# Mega_Shield_enjaksa.net
KiCad netlist of a schematic drawn in EAGLE
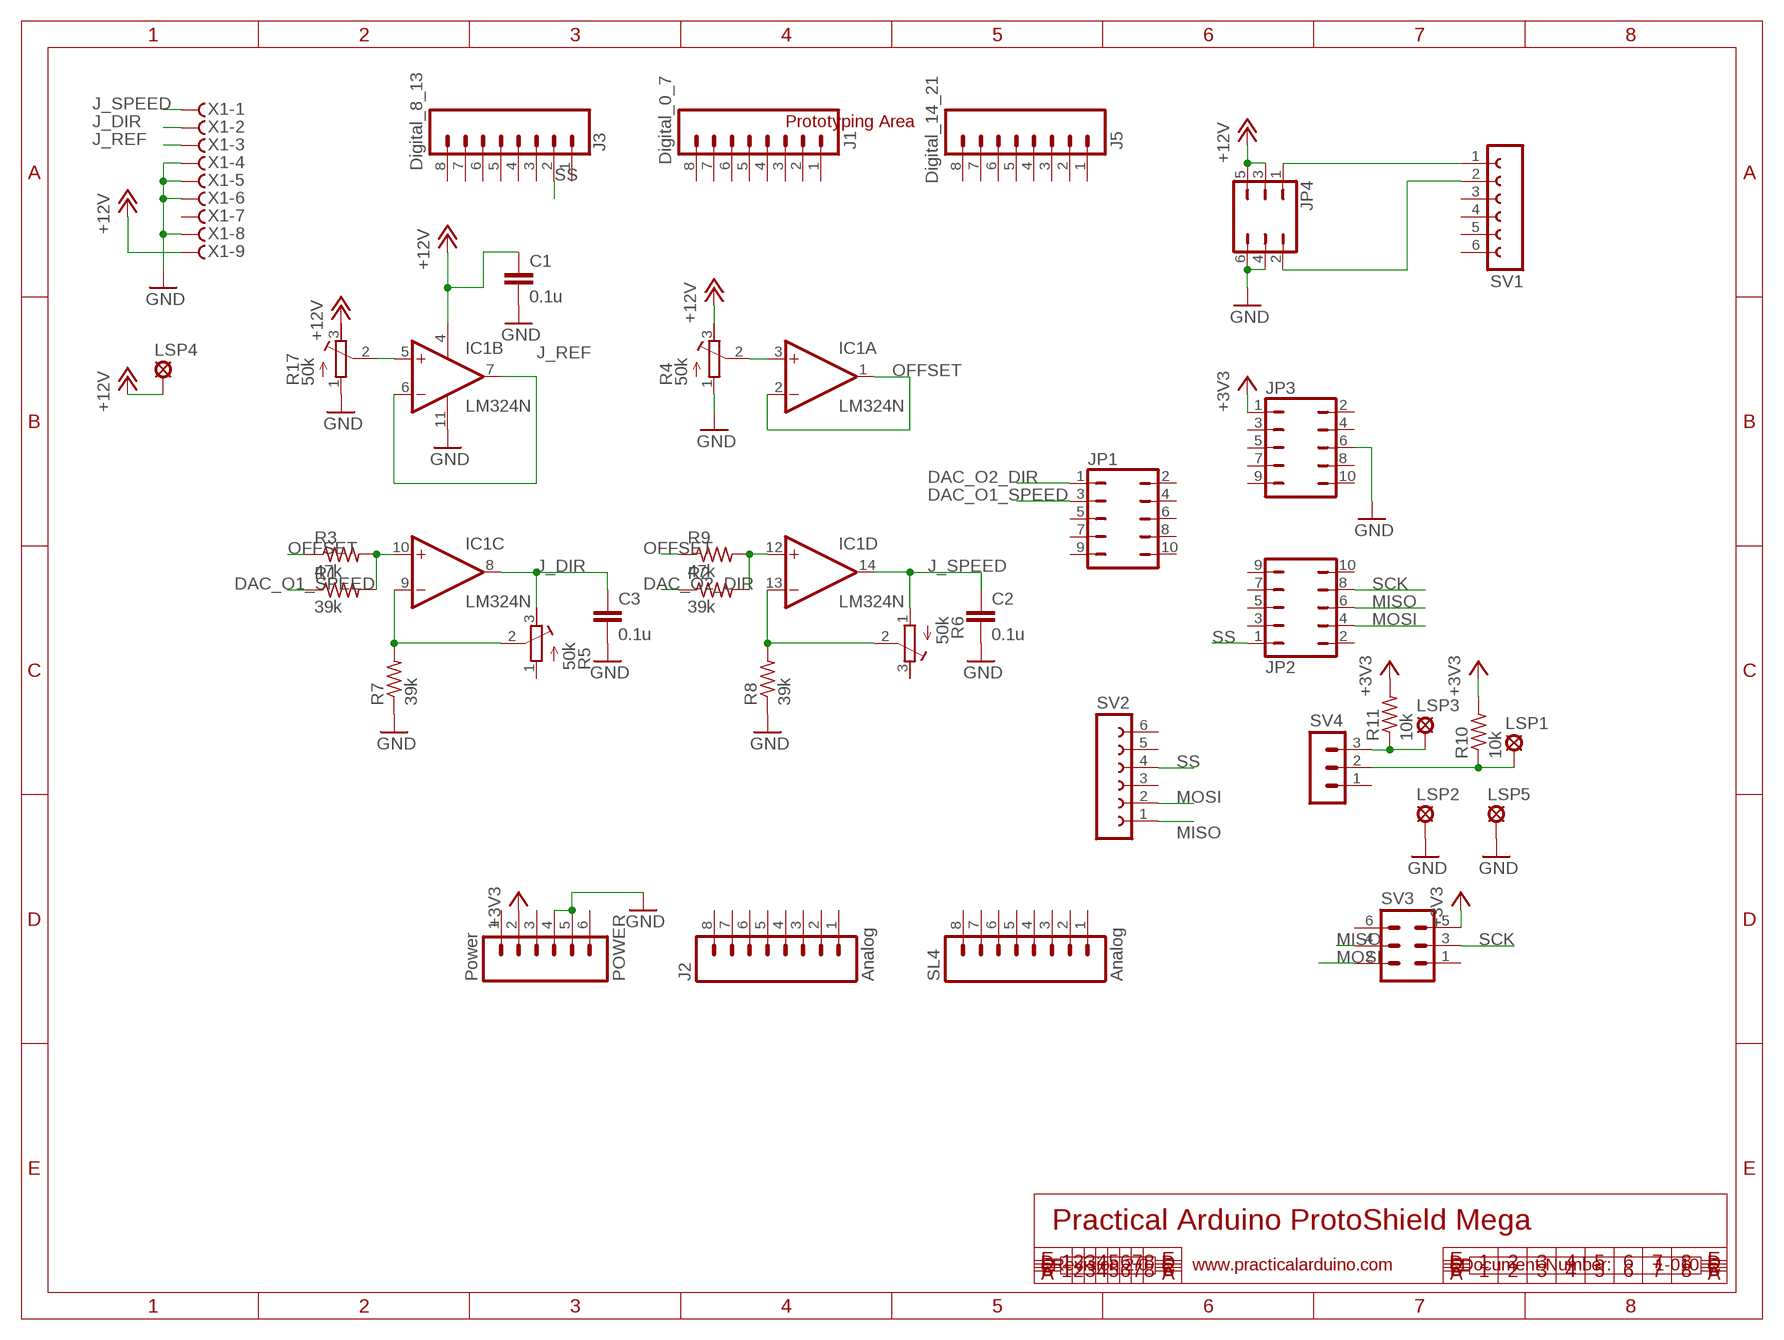
[diagram p0: schematic, sheet 1]

(export (version "E")
  (design (tool "Eeschema 10.0.6"))
  (components
    (comp (ref "C1")
      (value "0.1u")
      (footprint "eagle-import:C025-024X044")
      (libsource (lib "eagle-import") (part "C-EU025-024X044"))
    )
    (comp (ref "C2")
      (value "0.1u")
      (footprint "eagle-import:C050-025X075")
      (libsource (lib "eagle-import") (part "C-EU050-025X075"))
    )
    (comp (ref "C3")
      (value "0.1u")
      (footprint "eagle-import:C025-024X044")
      (libsource (lib "eagle-import") (part "C-EU025-024X044"))
    )
    (comp (ref "IC1")
      (value "LM324N")
      (footprint "eagle-import:DIL14")
      (libsource (lib "eagle-import") (part "LM324N"))
    )
    (comp (ref "J1")
      (value "Digital_0_7")
      (footprint "eagle-import:1X08")
      (libsource (lib "eagle-import") (part "M08"))
    )
    (comp (ref "J2")
      (value "Analog")
      (footprint "eagle-import:1X08")
      (libsource (lib "eagle-import") (part "M08"))
    )
    (comp (ref "J3")
      (value "Digital_8_13")
      (footprint "eagle-import:1X08")
      (libsource (lib "eagle-import") (part "M08"))
    )
    (comp (ref "J5")
      (value "Digital_14_21")
      (footprint "eagle-import:1X08")
      (libsource (lib "eagle-import") (part "M08"))
    )
    (comp (ref "JP1")
      (value "JP5Q")
      (footprint "eagle-import:JP5Q")
      (libsource (lib "eagle-import") (part "JP5Q"))
    )
    (comp (ref "JP2")
      (value "JP5Q")
      (footprint "eagle-import:JP5Q")
      (libsource (lib "eagle-import") (part "JP5Q"))
    )
    (comp (ref "JP3")
      (value "JP5Q")
      (footprint "eagle-import:JP5Q")
      (libsource (lib "eagle-import") (part "JP5Q"))
    )
    (comp (ref "JP4")
      (value "JP3Q")
      (footprint "eagle-import:JP3Q")
      (libsource (lib "eagle-import") (part "JP3Q"))
    )
    (comp (ref "LSP1")
      (value "SE13")
      (footprint "eagle-import:SE13")
      (libsource (lib "eagle-import") (part "SE13"))
    )
    (comp (ref "LSP2")
      (value "SE13")
      (footprint "eagle-import:SE13")
      (libsource (lib "eagle-import") (part "SE13"))
    )
    (comp (ref "LSP3")
      (value "SE13")
      (footprint "eagle-import:SE13")
      (libsource (lib "eagle-import") (part "SE13"))
    )
    (comp (ref "LSP4")
      (value "SE13")
      (footprint "eagle-import:SE13")
      (libsource (lib "eagle-import") (part "SE13"))
    )
    (comp (ref "LSP5")
      (value "SE13")
      (footprint "eagle-import:SE13")
      (libsource (lib "eagle-import") (part "SE13"))
    )
    (comp (ref "POWER")
      (value "Power")
      (footprint "eagle-import:1X06")
      (libsource (lib "eagle-import") (part "M06SIP"))
    )
    (comp (ref "R1")
      (value "39k")
      (footprint "eagle-import:0204_7")
      (libsource (lib "eagle-import") (part "R-US_0204/7"))
    )
    (comp (ref "R2")
      (value "39k")
      (footprint "eagle-import:0204_7")
      (libsource (lib "eagle-import") (part "R-US_0204/7"))
    )
    (comp (ref "R3")
      (value "47k")
      (footprint "eagle-import:0204_7")
      (libsource (lib "eagle-import") (part "R-US_0204/7"))
    )
    (comp (ref "R4")
      (value "50k")
      (footprint "eagle-import:RTRIM64W")
      (libsource (lib "eagle-import") (part "R-TRIMM64W"))
    )
    (comp (ref "R5")
      (value "50k")
      (footprint "eagle-import:RTRIM64W")
      (libsource (lib "eagle-import") (part "R-TRIMM64W"))
    )
    (comp (ref "R6")
      (value "50k")
      (footprint "eagle-import:RTRIM64W")
      (libsource (lib "eagle-import") (part "R-TRIMM64W"))
    )
    (comp (ref "R7")
      (value "39k")
      (footprint "eagle-import:0204_7")
      (libsource (lib "eagle-import") (part "R-US_0204/7"))
    )
    (comp (ref "R8")
      (value "39k")
      (footprint "eagle-import:0204V")
      (libsource (lib "eagle-import") (part "R-US_0204/2V"))
    )
    (comp (ref "R9")
      (value "47k")
      (footprint "eagle-import:0204_7")
      (libsource (lib "eagle-import") (part "R-US_0204/7"))
    )
    (comp (ref "R10")
      (value "10k")
      (footprint "eagle-import:0204V")
      (libsource (lib "eagle-import") (part "R-US_0204/2V"))
    )
    (comp (ref "R11")
      (value "10k")
      (footprint "eagle-import:0204V")
      (libsource (lib "eagle-import") (part "R-US_0204/2V"))
    )
    (comp (ref "R17")
      (value "50k")
      (footprint "eagle-import:RTRIM64W")
      (libsource (lib "eagle-import") (part "R-TRIMM64W"))
    )
    (comp (ref "SL4")
      (value "Analog")
      (footprint "eagle-import:1X08")
      (libsource (lib "eagle-import") (part "M08"))
    )
    (comp (ref "SV1")
      (value "FE06-1")
      (footprint "eagle-import:FE06")
      (libsource (lib "eagle-import") (part "FE06-1"))
    )
    (comp (ref "SV2")
      (value "FE06-1")
      (footprint "eagle-import:FE06")
      (libsource (lib "eagle-import") (part "FE06-1"))
    )
    (comp (ref "SV3")
      (value "MA03-2")
      (footprint "eagle-import:MA03-2")
      (libsource (lib "eagle-import") (part "MA03-2"))
    )
    (comp (ref "SV4")
      (value "MA03-1")
      (footprint "eagle-import:MA03-1")
      (libsource (lib "eagle-import") (part "MA03-1"))
    )
    (comp (ref "X1")
      (value "F09HS")
      (footprint "eagle-import:F09H")
      (libsource (lib "eagle-import") (part "F09?SH"))
    )
  )
  (nets
    (net (code "1") (name "+3V3") (class "Default")
      (node (ref "JP3") (pin "1") (pinfunction "1_1") (pintype "passive"))
      (node (ref "POWER") (pin "2") (pinfunction "2_2") (pintype "passive"))
      (node (ref "R10") (pin "2") (pinfunction "2_2") (pintype "passive"))
      (node (ref "R11") (pin "2") (pinfunction "2_2") (pintype "passive"))
      (node (ref "SV3") (pin "5") (pinfunction "5_5") (pintype "passive"))
    )
    (net (code "2") (name "+12V") (class "Default")
      (node (ref "C1") (pin "1") (pinfunction "1_1") (pintype "passive"))
      (node (ref "IC1") (pin "4") (pinfunction "V+_4") (pintype "power_in"))
      (node (ref "JP4") (pin "3") (pinfunction "3_3") (pintype "passive"))
      (node (ref "JP4") (pin "5") (pinfunction "5_5") (pintype "passive"))
      (node (ref "LSP4") (pin "MP") (pinfunction "MP_MP") (pintype "passive"))
      (node (ref "R17") (pin "3") (pinfunction "E_3") (pintype "passive"))
      (node (ref "R4") (pin "3") (pinfunction "E_3") (pintype "passive"))
      (node (ref "X1") (pin "9") (pinfunction "F_9") (pintype "passive"))
    )
    (net (code "3") (name "/DAC_O1_SPEED") (class "Default")
      (node (ref "JP1") (pin "3") (pinfunction "3_3") (pintype "passive"))
      (node (ref "R1") (pin "1") (pinfunction "1_1") (pintype "passive"))
    )
    (net (code "4") (name "/DAC_O2_DIR") (class "Default")
      (node (ref "JP1") (pin "1") (pinfunction "1_1") (pintype "passive"))
      (node (ref "R2") (pin "1") (pinfunction "1_1") (pintype "passive"))
    )
    (net (code "5") (name "/J_DIR") (class "Default")
      (node (ref "C3") (pin "1") (pinfunction "1_1") (pintype "passive"))
      (node (ref "IC1") (pin "8") (pinfunction "OUT_8") (pintype "output"))
      (node (ref "R5") (pin "3") (pinfunction "E_3") (pintype "passive"))
      (node (ref "X1") (pin "2") (pinfunction "F_2") (pintype "passive"))
    )
    (net (code "6") (name "/J_REF") (class "Default")
      (node (ref "IC1") (pin "6") (pinfunction "-IN_6") (pintype "input"))
      (node (ref "IC1") (pin "7") (pinfunction "OUT_7") (pintype "output"))
      (node (ref "X1") (pin "3") (pinfunction "F_3") (pintype "passive"))
    )
    (net (code "7") (name "/J_SPEED") (class "Default")
      (node (ref "C2") (pin "1") (pinfunction "1_1") (pintype "passive"))
      (node (ref "IC1") (pin "14") (pinfunction "OUT_14") (pintype "output"))
      (node (ref "R6") (pin "1") (pinfunction "A_1") (pintype "passive"))
      (node (ref "X1") (pin "1") (pinfunction "F_1") (pintype "passive"))
    )
    (net (code "8") (name "/MISO") (class "Default")
      (node (ref "JP2") (pin "6") (pinfunction "6_6") (pintype "passive"))
      (node (ref "SV2") (pin "1") (pinfunction "1_1") (pintype "passive"))
      (node (ref "SV3") (pin "4") (pinfunction "4_4") (pintype "passive"))
    )
    (net (code "9") (name "/MOSI") (class "Default")
      (node (ref "JP2") (pin "4") (pinfunction "4_4") (pintype "passive"))
      (node (ref "SV2") (pin "2") (pinfunction "2_2") (pintype "passive"))
      (node (ref "SV3") (pin "2") (pinfunction "2_2") (pintype "passive"))
    )
    (net (code "10") (name "/OFFSET") (class "Default")
      (node (ref "IC1") (pin "1") (pinfunction "OUT_1") (pintype "output"))
      (node (ref "IC1") (pin "2") (pinfunction "-IN_2") (pintype "input"))
      (node (ref "R3") (pin "1") (pinfunction "1_1") (pintype "passive"))
      (node (ref "R9") (pin "1") (pinfunction "1_1") (pintype "passive"))
    )
    (net (code "11") (name "/SCK") (class "Default")
      (node (ref "JP2") (pin "8") (pinfunction "8_8") (pintype "passive"))
      (node (ref "SV3") (pin "3") (pinfunction "3_3") (pintype "passive"))
    )
    (net (code "12") (name "/SS") (class "Default")
      (node (ref "J3") (pin "2") (pinfunction "2_2") (pintype "passive"))
      (node (ref "JP2") (pin "1") (pinfunction "1_1") (pintype "passive"))
      (node (ref "SV2") (pin "4") (pinfunction "4_4") (pintype "passive"))
    )
    (net (code "13") (name "GND") (class "Default")
      (node (ref "C1") (pin "2") (pinfunction "2_2") (pintype "passive"))
      (node (ref "C2") (pin "2") (pinfunction "2_2") (pintype "passive"))
      (node (ref "C3") (pin "2") (pinfunction "2_2") (pintype "passive"))
      (node (ref "IC1") (pin "11") (pinfunction "V-_11") (pintype "power_in"))
      (node (ref "JP3") (pin "6") (pinfunction "6_6") (pintype "passive"))
      (node (ref "JP4") (pin "4") (pinfunction "4_4") (pintype "passive"))
      (node (ref "JP4") (pin "6") (pinfunction "6_6") (pintype "passive"))
      (node (ref "LSP2") (pin "MP") (pinfunction "MP_MP") (pintype "passive"))
      (node (ref "LSP5") (pin "MP") (pinfunction "MP_MP") (pintype "passive"))
      (node (ref "POWER") (pin "4") (pinfunction "4_4") (pintype "passive"))
      (node (ref "POWER") (pin "5") (pinfunction "5_5") (pintype "passive"))
      (node (ref "R17") (pin "1") (pinfunction "A_1") (pintype "passive"))
      (node (ref "R4") (pin "1") (pinfunction "A_1") (pintype "passive"))
      (node (ref "R7") (pin "1") (pinfunction "1_1") (pintype "passive"))
      (node (ref "R8") (pin "1") (pinfunction "1_1") (pintype "passive"))
      (node (ref "X1") (pin "4") (pinfunction "F_4") (pintype "passive"))
      (node (ref "X1") (pin "5") (pinfunction "F_5") (pintype "passive"))
      (node (ref "X1") (pin "6") (pinfunction "F_6") (pintype "passive"))
      (node (ref "X1") (pin "8") (pinfunction "F_8") (pintype "passive"))
    )
    (net (code "14") (name "Net-(IC1A-+IN)") (class "Default")
      (node (ref "IC1") (pin "3") (pinfunction "+IN_3") (pintype "input"))
      (node (ref "R4") (pin "2") (pinfunction "S_2") (pintype "passive"))
    )
    (net (code "15") (name "Net-(IC1B-+IN)") (class "Default")
      (node (ref "IC1") (pin "5") (pinfunction "+IN_5") (pintype "input"))
      (node (ref "R17") (pin "2") (pinfunction "S_2") (pintype "passive"))
    )
    (net (code "16") (name "Net-(IC1C-+IN)") (class "Default")
      (node (ref "IC1") (pin "10") (pinfunction "+IN_10") (pintype "input"))
      (node (ref "R1") (pin "2") (pinfunction "2_2") (pintype "passive"))
      (node (ref "R3") (pin "2") (pinfunction "2_2") (pintype "passive"))
    )
    (net (code "17") (name "Net-(IC1C--IN)") (class "Default")
      (node (ref "IC1") (pin "9") (pinfunction "-IN_9") (pintype "input"))
      (node (ref "R5") (pin "2") (pinfunction "S_2") (pintype "passive"))
      (node (ref "R7") (pin "2") (pinfunction "2_2") (pintype "passive"))
    )
    (net (code "18") (name "Net-(IC1D-+IN)") (class "Default")
      (node (ref "IC1") (pin "12") (pinfunction "+IN_12") (pintype "input"))
      (node (ref "R2") (pin "2") (pinfunction "2_2") (pintype "passive"))
      (node (ref "R9") (pin "2") (pinfunction "2_2") (pintype "passive"))
    )
    (net (code "19") (name "Net-(IC1D--IN)") (class "Default")
      (node (ref "IC1") (pin "13") (pinfunction "-IN_13") (pintype "input"))
      (node (ref "R6") (pin "2") (pinfunction "S_2") (pintype "passive"))
      (node (ref "R8") (pin "2") (pinfunction "2_2") (pintype "passive"))
    )
    (net (code "20") (name "Net-(JP4-Pad1)") (class "Default")
      (node (ref "JP4") (pin "1") (pinfunction "1_1") (pintype "passive"))
      (node (ref "SV1") (pin "1") (pinfunction "1_1") (pintype "passive"))
    )
    (net (code "21") (name "Net-(JP4-Pad2)") (class "Default")
      (node (ref "JP4") (pin "2") (pinfunction "2_2") (pintype "passive"))
      (node (ref "SV1") (pin "2") (pinfunction "2_2") (pintype "passive"))
    )
    (net (code "22") (name "Net-(LSP1-PadMP)") (class "Default")
      (node (ref "LSP1") (pin "MP") (pinfunction "MP_MP") (pintype "passive"))
      (node (ref "R10") (pin "1") (pinfunction "1_1") (pintype "passive"))
      (node (ref "SV4") (pin "2") (pinfunction "2_2") (pintype "passive"))
    )
    (net (code "23") (name "Net-(LSP3-PadMP)") (class "Default")
      (node (ref "LSP3") (pin "MP") (pinfunction "MP_MP") (pintype "passive"))
      (node (ref "R11") (pin "1") (pinfunction "1_1") (pintype "passive"))
      (node (ref "SV4") (pin "3") (pinfunction "3_3") (pintype "passive"))
    )
    (net (code "24") (name "unconnected-(J1-Pad1)") (class "Default")
      (node (ref "J1") (pin "1") (pinfunction "1_1") (pintype "passive"))
    )
    (net (code "25") (name "unconnected-(J1-Pad2)") (class "Default")
      (node (ref "J1") (pin "2") (pinfunction "2_2") (pintype "passive"))
    )
    (net (code "26") (name "unconnected-(J1-Pad3)") (class "Default")
      (node (ref "J1") (pin "3") (pinfunction "3_3") (pintype "passive"))
    )
    (net (code "27") (name "unconnected-(J1-Pad4)") (class "Default")
      (node (ref "J1") (pin "4") (pinfunction "4_4") (pintype "passive"))
    )
    (net (code "28") (name "unconnected-(J1-Pad5)") (class "Default")
      (node (ref "J1") (pin "5") (pinfunction "5_5") (pintype "passive"))
    )
    (net (code "29") (name "unconnected-(J1-Pad6)") (class "Default")
      (node (ref "J1") (pin "6") (pinfunction "6_6") (pintype "passive"))
    )
    (net (code "30") (name "unconnected-(J1-Pad7)") (class "Default")
      (node (ref "J1") (pin "7") (pinfunction "7_7") (pintype "passive"))
    )
    (net (code "31") (name "unconnected-(J1-Pad8)") (class "Default")
      (node (ref "J1") (pin "8") (pinfunction "8_8") (pintype "passive"))
    )
    (net (code "32") (name "unconnected-(J2-Pad1)") (class "Default")
      (node (ref "J2") (pin "1") (pinfunction "1_1") (pintype "passive"))
    )
    (net (code "33") (name "unconnected-(J2-Pad2)") (class "Default")
      (node (ref "J2") (pin "2") (pinfunction "2_2") (pintype "passive"))
    )
    (net (code "34") (name "unconnected-(J2-Pad3)") (class "Default")
      (node (ref "J2") (pin "3") (pinfunction "3_3") (pintype "passive"))
    )
    (net (code "35") (name "unconnected-(J2-Pad4)") (class "Default")
      (node (ref "J2") (pin "4") (pinfunction "4_4") (pintype "passive"))
    )
    (net (code "36") (name "unconnected-(J2-Pad5)") (class "Default")
      (node (ref "J2") (pin "5") (pinfunction "5_5") (pintype "passive"))
    )
    (net (code "37") (name "unconnected-(J2-Pad6)") (class "Default")
      (node (ref "J2") (pin "6") (pinfunction "6_6") (pintype "passive"))
    )
    (net (code "38") (name "unconnected-(J2-Pad7)") (class "Default")
      (node (ref "J2") (pin "7") (pinfunction "7_7") (pintype "passive"))
    )
    (net (code "39") (name "unconnected-(J2-Pad8)") (class "Default")
      (node (ref "J2") (pin "8") (pinfunction "8_8") (pintype "passive"))
    )
    (net (code "40") (name "unconnected-(J3-Pad1)") (class "Default")
      (node (ref "J3") (pin "1") (pinfunction "1_1") (pintype "passive"))
    )
    (net (code "41") (name "unconnected-(J3-Pad3)") (class "Default")
      (node (ref "J3") (pin "3") (pinfunction "3_3") (pintype "passive"))
    )
    (net (code "42") (name "unconnected-(J3-Pad4)") (class "Default")
      (node (ref "J3") (pin "4") (pinfunction "4_4") (pintype "passive"))
    )
    (net (code "43") (name "unconnected-(J3-Pad5)") (class "Default")
      (node (ref "J3") (pin "5") (pinfunction "5_5") (pintype "passive"))
    )
    (net (code "44") (name "unconnected-(J3-Pad6)") (class "Default")
      (node (ref "J3") (pin "6") (pinfunction "6_6") (pintype "passive"))
    )
    (net (code "45") (name "unconnected-(J3-Pad7)") (class "Default")
      (node (ref "J3") (pin "7") (pinfunction "7_7") (pintype "passive"))
    )
    (net (code "46") (name "unconnected-(J3-Pad8)") (class "Default")
      (node (ref "J3") (pin "8") (pinfunction "8_8") (pintype "passive"))
    )
    (net (code "47") (name "unconnected-(J5-Pad1)") (class "Default")
      (node (ref "J5") (pin "1") (pinfunction "1_1") (pintype "passive"))
    )
    (net (code "48") (name "unconnected-(J5-Pad2)") (class "Default")
      (node (ref "J5") (pin "2") (pinfunction "2_2") (pintype "passive"))
    )
    (net (code "49") (name "unconnected-(J5-Pad3)") (class "Default")
      (node (ref "J5") (pin "3") (pinfunction "3_3") (pintype "passive"))
    )
    (net (code "50") (name "unconnected-(J5-Pad4)") (class "Default")
      (node (ref "J5") (pin "4") (pinfunction "4_4") (pintype "passive"))
    )
    (net (code "51") (name "unconnected-(J5-Pad5)") (class "Default")
      (node (ref "J5") (pin "5") (pinfunction "5_5") (pintype "passive"))
    )
    (net (code "52") (name "unconnected-(J5-Pad6)") (class "Default")
      (node (ref "J5") (pin "6") (pinfunction "6_6") (pintype "passive"))
    )
    (net (code "53") (name "unconnected-(J5-Pad7)") (class "Default")
      (node (ref "J5") (pin "7") (pinfunction "7_7") (pintype "passive"))
    )
    (net (code "54") (name "unconnected-(J5-Pad8)") (class "Default")
      (node (ref "J5") (pin "8") (pinfunction "8_8") (pintype "passive"))
    )
    (net (code "55") (name "unconnected-(JP1-Pad2)") (class "Default")
      (node (ref "JP1") (pin "2") (pinfunction "2_2") (pintype "passive"))
    )
    (net (code "56") (name "unconnected-(JP1-Pad4)") (class "Default")
      (node (ref "JP1") (pin "4") (pinfunction "4_4") (pintype "passive"))
    )
    (net (code "57") (name "unconnected-(JP1-Pad5)") (class "Default")
      (node (ref "JP1") (pin "5") (pinfunction "5_5") (pintype "passive"))
    )
    (net (code "58") (name "unconnected-(JP1-Pad6)") (class "Default")
      (node (ref "JP1") (pin "6") (pinfunction "6_6") (pintype "passive"))
    )
    (net (code "59") (name "unconnected-(JP1-Pad7)") (class "Default")
      (node (ref "JP1") (pin "7") (pinfunction "7_7") (pintype "passive"))
    )
    (net (code "60") (name "unconnected-(JP1-Pad8)") (class "Default")
      (node (ref "JP1") (pin "8") (pinfunction "8_8") (pintype "passive"))
    )
    (net (code "61") (name "unconnected-(JP1-Pad9)") (class "Default")
      (node (ref "JP1") (pin "9") (pinfunction "9_9") (pintype "passive"))
    )
    (net (code "62") (name "unconnected-(JP1-Pad10)") (class "Default")
      (node (ref "JP1") (pin "10") (pinfunction "10_10") (pintype "passive"))
    )
    (net (code "63") (name "unconnected-(JP2-Pad2)") (class "Default")
      (node (ref "JP2") (pin "2") (pinfunction "2_2") (pintype "passive"))
    )
    (net (code "64") (name "unconnected-(JP2-Pad3)") (class "Default")
      (node (ref "JP2") (pin "3") (pinfunction "3_3") (pintype "passive"))
    )
    (net (code "65") (name "unconnected-(JP2-Pad5)") (class "Default")
      (node (ref "JP2") (pin "5") (pinfunction "5_5") (pintype "passive"))
    )
    (net (code "66") (name "unconnected-(JP2-Pad7)") (class "Default")
      (node (ref "JP2") (pin "7") (pinfunction "7_7") (pintype "passive"))
    )
    (net (code "67") (name "unconnected-(JP2-Pad9)") (class "Default")
      (node (ref "JP2") (pin "9") (pinfunction "9_9") (pintype "passive"))
    )
    (net (code "68") (name "unconnected-(JP2-Pad10)") (class "Default")
      (node (ref "JP2") (pin "10") (pinfunction "10_10") (pintype "passive"))
    )
    (net (code "69") (name "unconnected-(JP3-Pad2)") (class "Default")
      (node (ref "JP3") (pin "2") (pinfunction "2_2") (pintype "passive"))
    )
    (net (code "70") (name "unconnected-(JP3-Pad3)") (class "Default")
      (node (ref "JP3") (pin "3") (pinfunction "3_3") (pintype "passive"))
    )
    (net (code "71") (name "unconnected-(JP3-Pad4)") (class "Default")
      (node (ref "JP3") (pin "4") (pinfunction "4_4") (pintype "passive"))
    )
    (net (code "72") (name "unconnected-(JP3-Pad5)") (class "Default")
      (node (ref "JP3") (pin "5") (pinfunction "5_5") (pintype "passive"))
    )
    (net (code "73") (name "unconnected-(JP3-Pad7)") (class "Default")
      (node (ref "JP3") (pin "7") (pinfunction "7_7") (pintype "passive"))
    )
    (net (code "74") (name "unconnected-(JP3-Pad8)") (class "Default")
      (node (ref "JP3") (pin "8") (pinfunction "8_8") (pintype "passive"))
    )
    (net (code "75") (name "unconnected-(JP3-Pad9)") (class "Default")
      (node (ref "JP3") (pin "9") (pinfunction "9_9") (pintype "passive"))
    )
    (net (code "76") (name "unconnected-(JP3-Pad10)") (class "Default")
      (node (ref "JP3") (pin "10") (pinfunction "10_10") (pintype "passive"))
    )
    (net (code "77") (name "unconnected-(POWER-Pad1)") (class "Default")
      (node (ref "POWER") (pin "1") (pinfunction "1_1") (pintype "passive"))
    )
    (net (code "78") (name "unconnected-(POWER-Pad3)") (class "Default")
      (node (ref "POWER") (pin "3") (pinfunction "3_3") (pintype "passive"))
    )
    (net (code "79") (name "unconnected-(POWER-Pad6)") (class "Default")
      (node (ref "POWER") (pin "6") (pinfunction "6_6") (pintype "passive"))
    )
    (net (code "80") (name "unconnected-(R5-A-Pad1)") (class "Default")
      (node (ref "R5") (pin "1") (pinfunction "A_1") (pintype "passive"))
    )
    (net (code "81") (name "unconnected-(R6-E-Pad3)") (class "Default")
      (node (ref "R6") (pin "3") (pinfunction "E_3") (pintype "passive"))
    )
    (net (code "82") (name "unconnected-(SL4-Pad1)") (class "Default")
      (node (ref "SL4") (pin "1") (pinfunction "1_1") (pintype "passive"))
    )
    (net (code "83") (name "unconnected-(SL4-Pad2)") (class "Default")
      (node (ref "SL4") (pin "2") (pinfunction "2_2") (pintype "passive"))
    )
    (net (code "84") (name "unconnected-(SL4-Pad3)") (class "Default")
      (node (ref "SL4") (pin "3") (pinfunction "3_3") (pintype "passive"))
    )
    (net (code "85") (name "unconnected-(SL4-Pad4)") (class "Default")
      (node (ref "SL4") (pin "4") (pinfunction "4_4") (pintype "passive"))
    )
    (net (code "86") (name "unconnected-(SL4-Pad5)") (class "Default")
      (node (ref "SL4") (pin "5") (pinfunction "5_5") (pintype "passive"))
    )
    (net (code "87") (name "unconnected-(SL4-Pad6)") (class "Default")
      (node (ref "SL4") (pin "6") (pinfunction "6_6") (pintype "passive"))
    )
    (net (code "88") (name "unconnected-(SL4-Pad7)") (class "Default")
      (node (ref "SL4") (pin "7") (pinfunction "7_7") (pintype "passive"))
    )
    (net (code "89") (name "unconnected-(SL4-Pad8)") (class "Default")
      (node (ref "SL4") (pin "8") (pinfunction "8_8") (pintype "passive"))
    )
    (net (code "90") (name "unconnected-(SV1-Pad3)") (class "Default")
      (node (ref "SV1") (pin "3") (pinfunction "3_3") (pintype "passive"))
    )
    (net (code "91") (name "unconnected-(SV1-Pad4)") (class "Default")
      (node (ref "SV1") (pin "4") (pinfunction "4_4") (pintype "passive"))
    )
    (net (code "92") (name "unconnected-(SV1-Pad5)") (class "Default")
      (node (ref "SV1") (pin "5") (pinfunction "5_5") (pintype "passive"))
    )
    (net (code "93") (name "unconnected-(SV1-Pad6)") (class "Default")
      (node (ref "SV1") (pin "6") (pinfunction "6_6") (pintype "passive"))
    )
    (net (code "94") (name "unconnected-(SV2-Pad3)") (class "Default")
      (node (ref "SV2") (pin "3") (pinfunction "3_3") (pintype "passive"))
    )
    (net (code "95") (name "unconnected-(SV2-Pad5)") (class "Default")
      (node (ref "SV2") (pin "5") (pinfunction "5_5") (pintype "passive"))
    )
    (net (code "96") (name "unconnected-(SV2-Pad6)") (class "Default")
      (node (ref "SV2") (pin "6") (pinfunction "6_6") (pintype "passive"))
    )
    (net (code "97") (name "unconnected-(SV3-Pad1)") (class "Default")
      (node (ref "SV3") (pin "1") (pinfunction "1_1") (pintype "passive"))
    )
    (net (code "98") (name "unconnected-(SV3-Pad6)") (class "Default")
      (node (ref "SV3") (pin "6") (pinfunction "6_6") (pintype "passive"))
    )
    (net (code "99") (name "unconnected-(SV4-Pad1)") (class "Default")
      (node (ref "SV4") (pin "1") (pinfunction "1_1") (pintype "passive"))
    )
    (net (code "100") (name "unconnected-(X1G-F-Pad7)") (class "Default")
      (node (ref "X1") (pin "7") (pinfunction "F_7") (pintype "passive"))
    )
  )
)
